# Handheld.net
KiCad netlist of a schematic drawn in EasyEDA
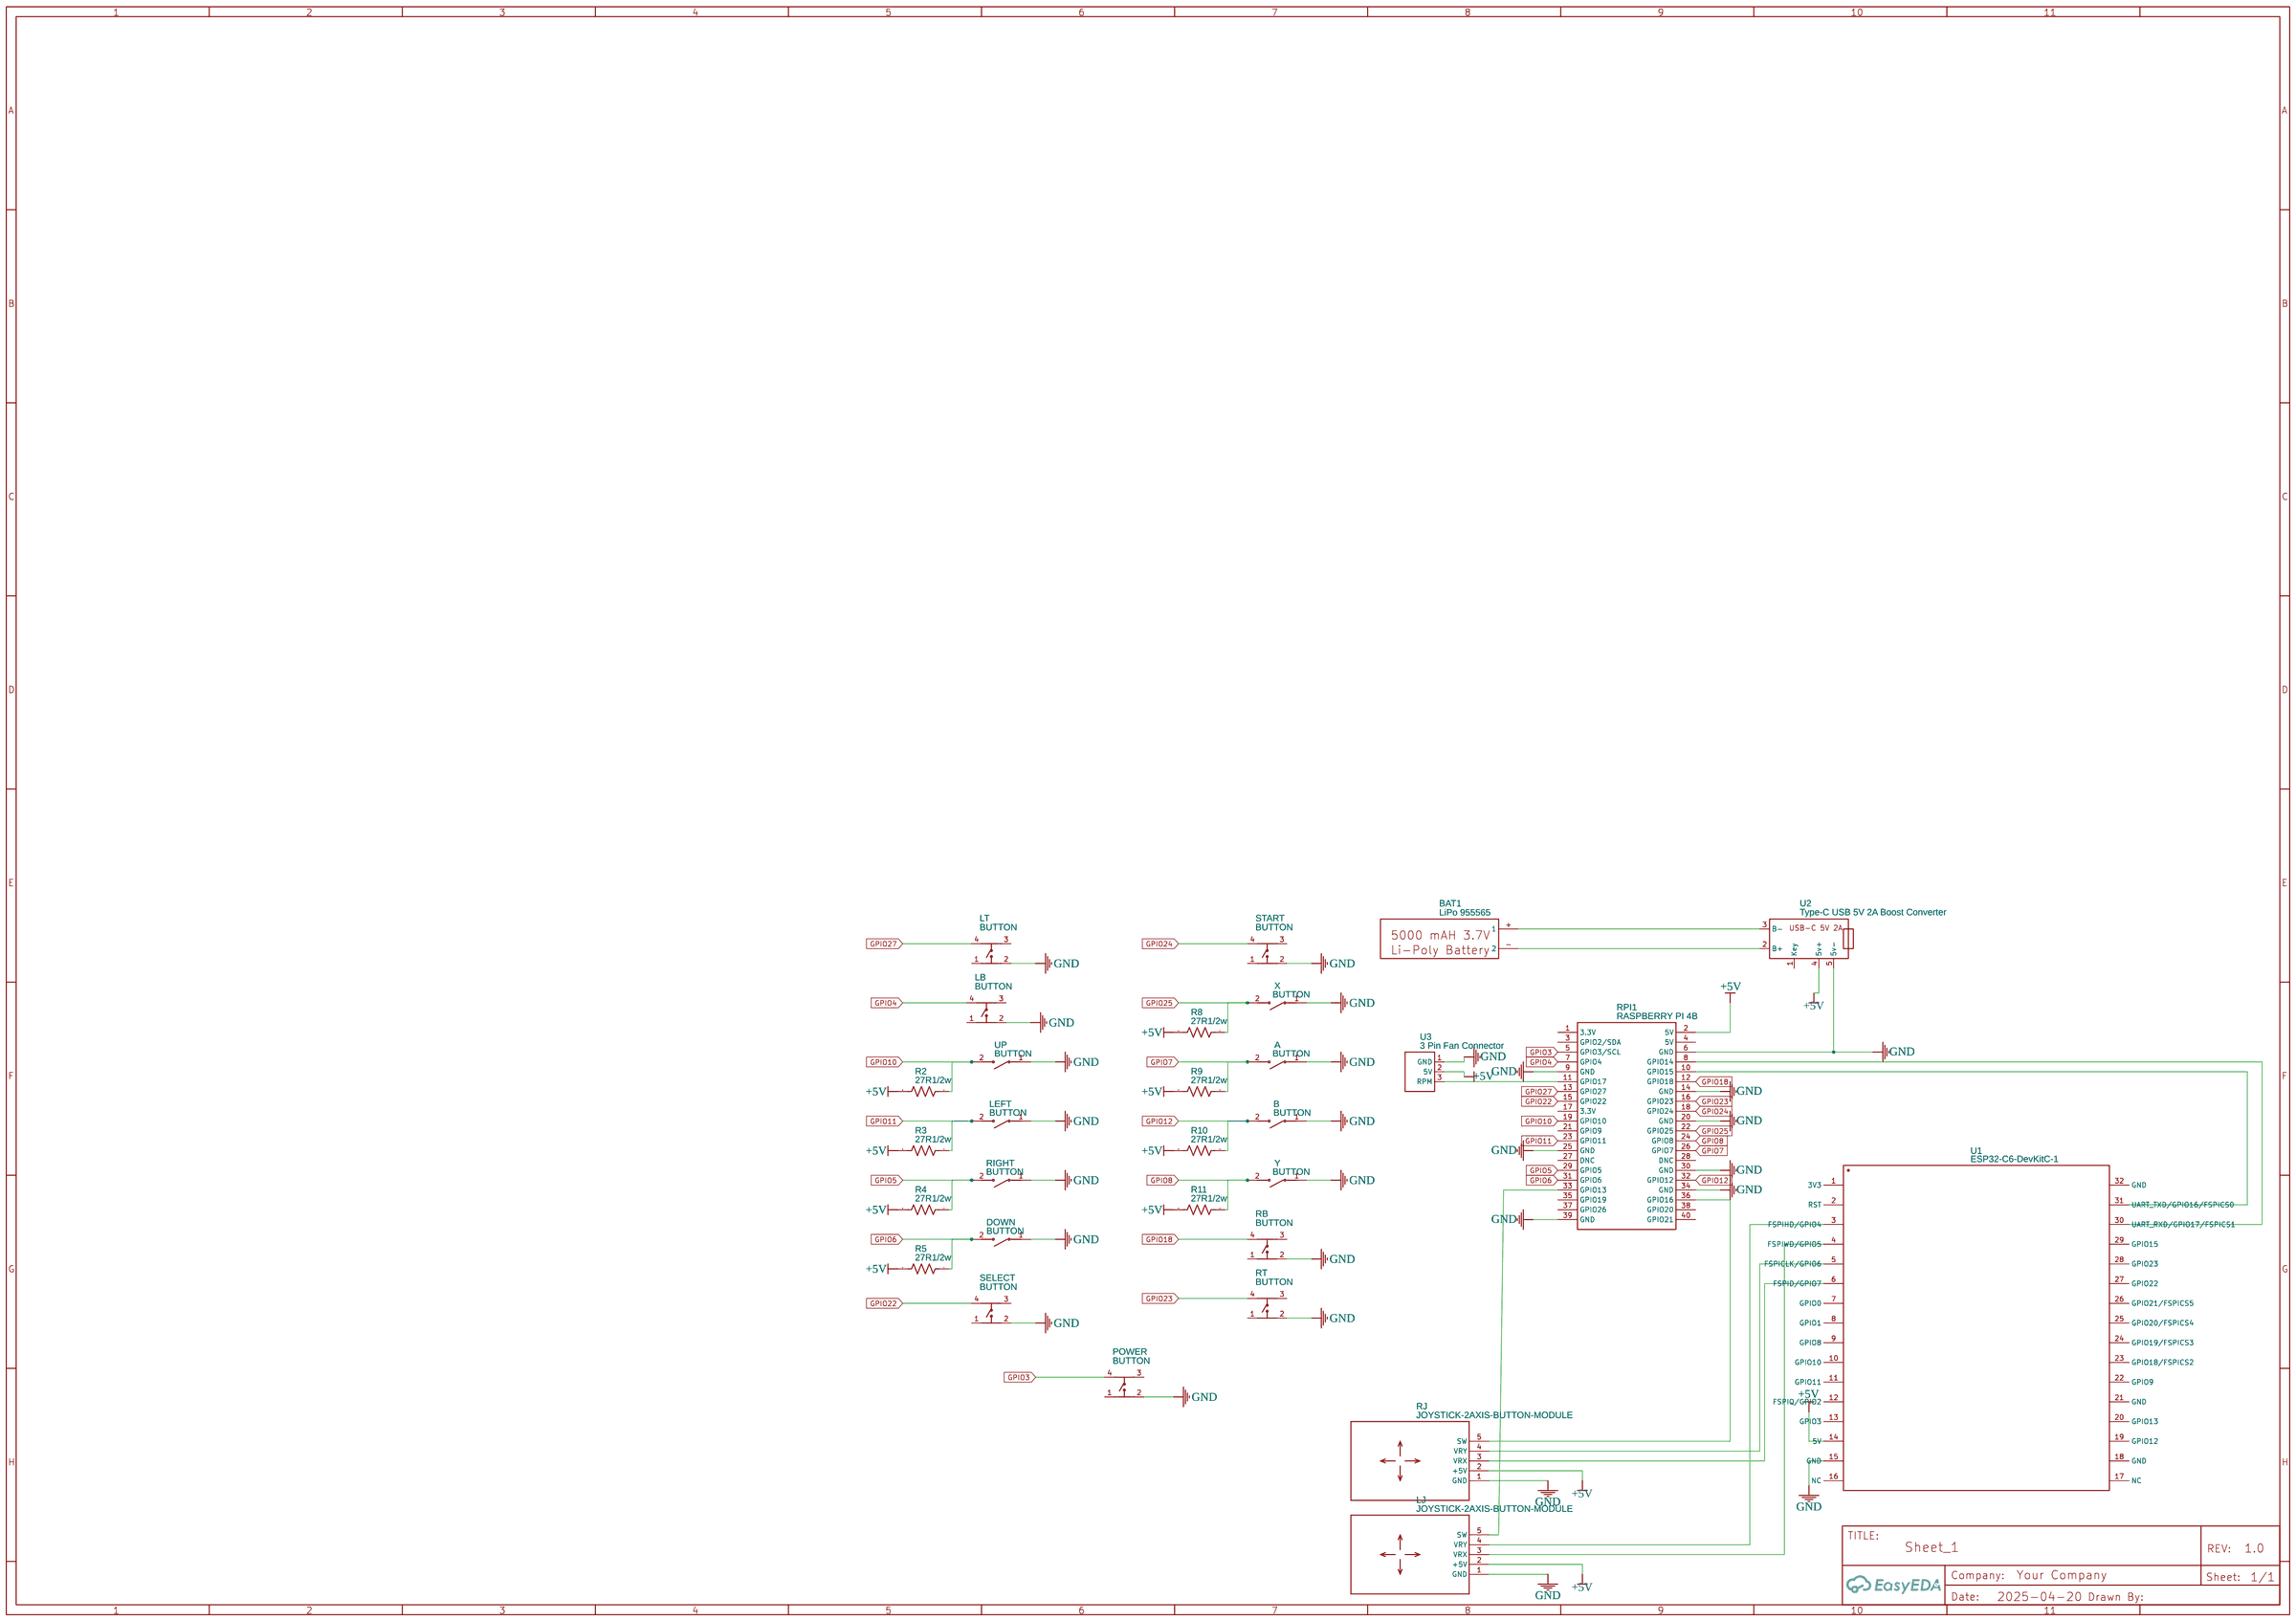
[diagram p0: schematic sheet]

(export (version "E")
  (design (tool "Eeschema 10.0.6"))
  (components
    (comp (ref "A") (value "BUTTON") (libsource (lib "") (part "BUTTON_4")))
    (comp (ref "B") (value "BUTTON") (libsource (lib "") (part "BUTTON_2")))
    (comp (ref "BAT1") (value "LiPo 955565") (libsource (lib "") (part "LiPo 955565")))
    (comp (ref "DOWN") (value "BUTTON") (libsource (lib "") (part "BUTTON_3")))
    (comp (ref "LB")
      (value "BUTTON")
      (fields (field (name "Manufacturer Part") "button6*6*8") (field (name "Manufacturer") "ReliaPro"))
      (libsource (lib "") (part "button6*6*8_5"))
    )
    (comp (ref "LEFT") (value "BUTTON") (libsource (lib "") (part "BUTTON_5")))
    (comp (ref "LJ")
      (value "JOYSTICK-2AXIS-BUTTON-MODULE")
      (libsource (lib "") (part "JOYSTICK-2AXIS-BUTTON-MODULE"))
    )
    (comp (ref "LT")
      (value "BUTTON")
      (fields (field (name "Manufacturer Part") "button6*6*8") (field (name "Manufacturer") "ReliaPro"))
      (libsource (lib "") (part "button6*6*8_6"))
    )
    (comp (ref "POWER")
      (value "BUTTON")
      (fields (field (name "Manufacturer Part") "button6*6*8") (field (name "Manufacturer") "ReliaPro"))
      (libsource (lib "") (part "button6*6*8_1"))
    )
    (comp (ref "R2") (value "27R1/2w") (libsource (lib "") (part "Resistor-1/2w")))
    (comp (ref "R3") (value "27R1/2w") (libsource (lib "") (part "Resistor-1/2w")))
    (comp (ref "R4") (value "27R1/2w") (libsource (lib "") (part "Resistor-1/2w")))
    (comp (ref "R5") (value "27R1/2w") (libsource (lib "") (part "Resistor-1/2w")))
    (comp (ref "R8") (value "27R1/2w") (libsource (lib "") (part "Resistor-1/2w")))
    (comp (ref "R9") (value "27R1/2w") (libsource (lib "") (part "Resistor-1/2w")))
    (comp (ref "R10") (value "27R1/2w") (libsource (lib "") (part "Resistor-1/2w")))
    (comp (ref "R11") (value "27R1/2w") (libsource (lib "") (part "Resistor-1/2w")))
    (comp (ref "RB")
      (value "BUTTON")
      (fields (field (name "Manufacturer Part") "button6*6*8") (field (name "Manufacturer") "ReliaPro"))
      (libsource (lib "") (part "button6*6*8_2"))
    )
    (comp (ref "RIGHT") (value "BUTTON") (libsource (lib "") (part "BUTTON_1")))
    (comp (ref "RJ")
      (value "JOYSTICK-2AXIS-BUTTON-MODULE")
      (libsource (lib "") (part "JOYSTICK-2AXIS-BUTTON-MODULE_1"))
    )
    (comp (ref "RPI1")
      (value "RASPBERRY PI 4B")
      (fields
        (field (name "Manufacturer Part") "Raspberry Pi 4 Model B 2019 Quad Core 64 Bit WiFi Bluetooth (4GB)")
        (field (name "Manufacturer") "Raspberry Pi")
      )
      (libsource (lib "") (part "RASPBERRY PI 4B"))
    )
    (comp (ref "RT")
      (value "BUTTON")
      (fields (field (name "Manufacturer Part") "button6*6*8") (field (name "Manufacturer") "ReliaPro"))
      (libsource (lib "") (part "button6*6*8_4"))
    )
    (comp (ref "SELECT")
      (value "BUTTON")
      (fields (field (name "Manufacturer Part") "button6*6*8") (field (name "Manufacturer") "ReliaPro"))
      (libsource (lib "") (part "button6*6*8_3"))
    )
    (comp (ref "START")
      (value "BUTTON")
      (fields (field (name "Manufacturer Part") "button6*6*8") (field (name "Manufacturer") "ReliaPro"))
      (libsource (lib "") (part "button6*6*8"))
    )
    (comp (ref "U1") (value "ESP32-C6-DevKitC-1") (libsource (lib "") (part "ESP32-C6-DevKitC-1")))
    (comp (ref "U2")
      (value "Type-C USB 5V 2A Boost Converter")
      (fields (field (name "Manufacturer Part") "ELC5060"))
      (libsource (lib "") (part "Type-C USB 5V 2A Boost Converter"))
    )
    (comp (ref "U3")
      (value "3 Pin Fan Connector")
      (fields (field (name "Manufacturer Part") "PSS 254/3W"))
      (libsource (lib "") (part "3 Pin Fan Connector"))
    )
    (comp (ref "UP") (value "BUTTON") (libsource (lib "") (part "BUTTON_6")))
    (comp (ref "X") (value "BUTTON") (libsource (lib "") (part "BUTTON")))
    (comp (ref "Y") (value "BUTTON") (libsource (lib "") (part "BUTTON_7")))
  )
  (nets
    (net (code "1") (name "+5V") (class "Default")
      (node (ref "LJ") (pin "2") (pinfunction "+5V_2") (pintype "bidirectional"))
      (node (ref "R10") (pin "2") (pinfunction "2_2") (pintype "unspecified"))
      (node (ref "R11") (pin "2") (pinfunction "2_2") (pintype "unspecified"))
      (node (ref "R2") (pin "2") (pinfunction "2_2") (pintype "unspecified"))
      (node (ref "R3") (pin "2") (pinfunction "2_2") (pintype "unspecified"))
      (node (ref "R4") (pin "2") (pinfunction "2_2") (pintype "unspecified"))
      (node (ref "R5") (pin "2") (pinfunction "2_2") (pintype "unspecified"))
      (node (ref "R8") (pin "2") (pinfunction "2_2") (pintype "unspecified"))
      (node (ref "R9") (pin "2") (pinfunction "2_2") (pintype "unspecified"))
      (node (ref "RJ") (pin "2") (pinfunction "+5V_2") (pintype "bidirectional"))
      (node (ref "RPI1") (pin "2") (pinfunction "5V_2") (pintype "unspecified"))
      (node (ref "U1") (pin "14") (pinfunction "5V_14") (pintype "unspecified"))
      (node (ref "U2") (pin "4") (pinfunction "5v+_4") (pintype "passive"))
      (node (ref "U3") (pin "2") (pinfunction "5V_2") (pintype "unspecified"))
    )
    (net (code "2") (name "GND") (class "Default")
      (node (ref "A") (pin "1") (pinfunction "1_1") (pintype "unspecified"))
      (node (ref "B") (pin "1") (pinfunction "1_1") (pintype "unspecified"))
      (node (ref "DOWN") (pin "1") (pinfunction "1_1") (pintype "unspecified"))
      (node (ref "LB") (pin "2") (pinfunction "2_2") (pintype "unspecified"))
      (node (ref "LEFT") (pin "1") (pinfunction "1_1") (pintype "unspecified"))
      (node (ref "LJ") (pin "1") (pinfunction "GND_1") (pintype "bidirectional"))
      (node (ref "LT") (pin "2") (pinfunction "2_2") (pintype "unspecified"))
      (node (ref "POWER") (pin "2") (pinfunction "2_2") (pintype "unspecified"))
      (node (ref "RB") (pin "2") (pinfunction "2_2") (pintype "unspecified"))
      (node (ref "RIGHT") (pin "1") (pinfunction "1_1") (pintype "unspecified"))
      (node (ref "RJ") (pin "1") (pinfunction "GND_1") (pintype "bidirectional"))
      (node (ref "RPI1") (pin "14") (pinfunction "GND_14") (pintype "unspecified"))
      (node (ref "RPI1") (pin "20") (pinfunction "GND_20") (pintype "unspecified"))
      (node (ref "RPI1") (pin "25") (pinfunction "GND_25") (pintype "unspecified"))
      (node (ref "RPI1") (pin "30") (pinfunction "GND_30") (pintype "unspecified"))
      (node (ref "RPI1") (pin "34") (pinfunction "GND_34") (pintype "unspecified"))
      (node (ref "RPI1") (pin "39") (pinfunction "GND_39") (pintype "unspecified"))
      (node (ref "RPI1") (pin "6") (pinfunction "GND_6") (pintype "unspecified"))
      (node (ref "RPI1") (pin "9") (pinfunction "GND_9") (pintype "unspecified"))
      (node (ref "RT") (pin "2") (pinfunction "2_2") (pintype "unspecified"))
      (node (ref "SELECT") (pin "2") (pinfunction "2_2") (pintype "unspecified"))
      (node (ref "START") (pin "2") (pinfunction "2_2") (pintype "unspecified"))
      (node (ref "U1") (pin "15") (pinfunction "GND_15") (pintype "unspecified"))
      (node (ref "U2") (pin "5") (pinfunction "5v-_5") (pintype "passive"))
      (node (ref "U3") (pin "1") (pinfunction "GND_1") (pintype "unspecified"))
      (node (ref "UP") (pin "1") (pinfunction "1_1") (pintype "unspecified"))
      (node (ref "X") (pin "1") (pinfunction "1_1") (pintype "unspecified"))
      (node (ref "Y") (pin "1") (pinfunction "1_1") (pintype "unspecified"))
    )
    (net (code "3") (name "GPIO3") (class "Default")
      (node (ref "POWER") (pin "4") (pinfunction "4_4") (pintype "unspecified"))
      (node (ref "RPI1") (pin "5") (pinfunction "GPIO3/SCL_5") (pintype "unspecified"))
    )
    (net (code "4") (name "GPIO4") (class "Default")
      (node (ref "LB") (pin "4") (pinfunction "4_4") (pintype "unspecified"))
      (node (ref "RPI1") (pin "7") (pinfunction "GPIO4_7") (pintype "unspecified"))
    )
    (net (code "5") (name "GPIO5") (class "Default")
      (node (ref "R4") (pin "1") (pinfunction "1_1") (pintype "unspecified"))
      (node (ref "RIGHT") (pin "2") (pinfunction "2_2") (pintype "unspecified"))
      (node (ref "RPI1") (pin "29") (pinfunction "GPIO5_29") (pintype "unspecified"))
    )
    (net (code "6") (name "GPIO6") (class "Default")
      (node (ref "DOWN") (pin "2") (pinfunction "2_2") (pintype "unspecified"))
      (node (ref "R5") (pin "1") (pinfunction "1_1") (pintype "unspecified"))
      (node (ref "RPI1") (pin "31") (pinfunction "GPIO6_31") (pintype "unspecified"))
    )
    (net (code "7") (name "GPIO7") (class "Default")
      (node (ref "A") (pin "2") (pinfunction "2_2") (pintype "unspecified"))
      (node (ref "R9") (pin "1") (pinfunction "1_1") (pintype "unspecified"))
      (node (ref "RPI1") (pin "26") (pinfunction "GPIO7_26") (pintype "unspecified"))
    )
    (net (code "8") (name "GPIO8") (class "Default")
      (node (ref "R11") (pin "1") (pinfunction "1_1") (pintype "unspecified"))
      (node (ref "RPI1") (pin "24") (pinfunction "GPIO8_24") (pintype "unspecified"))
      (node (ref "Y") (pin "2") (pinfunction "2_2") (pintype "unspecified"))
    )
    (net (code "9") (name "GPIO10") (class "Default")
      (node (ref "R2") (pin "1") (pinfunction "1_1") (pintype "unspecified"))
      (node (ref "RPI1") (pin "19") (pinfunction "GPIO10_19") (pintype "unspecified"))
      (node (ref "UP") (pin "2") (pinfunction "2_2") (pintype "unspecified"))
    )
    (net (code "10") (name "GPIO11") (class "Default")
      (node (ref "LEFT") (pin "2") (pinfunction "2_2") (pintype "unspecified"))
      (node (ref "R3") (pin "1") (pinfunction "1_1") (pintype "unspecified"))
      (node (ref "RPI1") (pin "23") (pinfunction "GPIO11_23") (pintype "unspecified"))
    )
    (net (code "11") (name "GPIO12") (class "Default")
      (node (ref "B") (pin "2") (pinfunction "2_2") (pintype "unspecified"))
      (node (ref "R10") (pin "1") (pinfunction "1_1") (pintype "unspecified"))
      (node (ref "RPI1") (pin "32") (pinfunction "GPIO12_32") (pintype "unspecified"))
    )
    (net (code "12") (name "GPIO18") (class "Default")
      (node (ref "RB") (pin "4") (pinfunction "4_4") (pintype "unspecified"))
      (node (ref "RPI1") (pin "12") (pinfunction "GPIO18_12") (pintype "unspecified"))
    )
    (net (code "13") (name "GPIO22") (class "Default")
      (node (ref "RPI1") (pin "15") (pinfunction "GPIO22_15") (pintype "unspecified"))
      (node (ref "SELECT") (pin "4") (pinfunction "4_4") (pintype "unspecified"))
    )
    (net (code "14") (name "GPIO23") (class "Default")
      (node (ref "RPI1") (pin "16") (pinfunction "GPIO23_16") (pintype "unspecified"))
      (node (ref "RT") (pin "4") (pinfunction "4_4") (pintype "unspecified"))
    )
    (net (code "15") (name "GPIO24") (class "Default")
      (node (ref "RPI1") (pin "18") (pinfunction "GPIO24_18") (pintype "unspecified"))
      (node (ref "START") (pin "4") (pinfunction "4_4") (pintype "unspecified"))
    )
    (net (code "16") (name "GPIO25") (class "Default")
      (node (ref "R8") (pin "1") (pinfunction "1_1") (pintype "unspecified"))
      (node (ref "RPI1") (pin "22") (pinfunction "GPIO25_22") (pintype "unspecified"))
      (node (ref "X") (pin "2") (pinfunction "2_2") (pintype "unspecified"))
    )
    (net (code "17") (name "GPIO27") (class "Default")
      (node (ref "LT") (pin "4") (pinfunction "4_4") (pintype "unspecified"))
      (node (ref "RPI1") (pin "13") (pinfunction "GPIO27_13") (pintype "unspecified"))
    )
    (net (code "18") (name "Net-(BAT1-1)") (class "Default")
      (node (ref "BAT1") (pin "+") (pinfunction "1_+") (pintype "unspecified"))
      (node (ref "U2") (pin "3") (pinfunction "B-_3") (pintype "input"))
    )
    (net (code "19") (name "Net-(BAT1-2)") (class "Default")
      (node (ref "BAT1") (pin "-") (pinfunction "2_-") (pintype "unspecified"))
      (node (ref "U2") (pin "2") (pinfunction "B+_2") (pintype "input"))
    )
    (net (code "20") (name "Net-(LJ-SW)") (class "Default")
      (node (ref "LJ") (pin "5") (pinfunction "SW_5") (pintype "bidirectional"))
      (node (ref "RPI1") (pin "33") (pinfunction "GPIO13_33") (pintype "unspecified"))
    )
    (net (code "21") (name "Net-(LJ-VRX)") (class "Default")
      (node (ref "LJ") (pin "3") (pinfunction "VRX_3") (pintype "bidirectional"))
      (node (ref "U1") (pin "4") (pinfunction "FSPIWD/GPIO5_4") (pintype "unspecified"))
    )
    (net (code "22") (name "Net-(LJ-VRY)") (class "Default")
      (node (ref "LJ") (pin "4") (pinfunction "VRY_4") (pintype "bidirectional"))
      (node (ref "U1") (pin "3") (pinfunction "FSPIHD/GPIO4_3") (pintype "unspecified"))
    )
    (net (code "23") (name "Net-(RJ-SW)") (class "Default")
      (node (ref "RJ") (pin "5") (pinfunction "SW_5") (pintype "bidirectional"))
      (node (ref "RPI1") (pin "36") (pinfunction "GPIO16_36") (pintype "unspecified"))
    )
    (net (code "24") (name "Net-(RJ-VRX)") (class "Default")
      (node (ref "RJ") (pin "3") (pinfunction "VRX_3") (pintype "bidirectional"))
      (node (ref "U1") (pin "6") (pinfunction "FSPID/GPIO7_6") (pintype "unspecified"))
    )
    (net (code "25") (name "Net-(RJ-VRY)") (class "Default")
      (node (ref "RJ") (pin "4") (pinfunction "VRY_4") (pintype "bidirectional"))
      (node (ref "U1") (pin "5") (pinfunction "FSPICLK/GPIO6_5") (pintype "unspecified"))
    )
    (net (code "26") (name "Net-(RPI1-GPIO14)") (class "Default")
      (node (ref "RPI1") (pin "8") (pinfunction "GPIO14_8") (pintype "unspecified"))
      (node (ref "U1") (pin "30") (pinfunction "UART_RXD/GPIO17/FSPICS1_30") (pintype "unspecified"))
    )
    (net (code "27") (name "Net-(RPI1-GPIO15)") (class "Default")
      (node (ref "RPI1") (pin "10") (pinfunction "GPIO15_10") (pintype "unspecified"))
      (node (ref "U1") (pin "31") (pinfunction "UART_TXD/GPIO16/FSPICS0_31") (pintype "unspecified"))
    )
    (net (code "28") (name "Net-(RPI1-GPIO17)") (class "Default")
      (node (ref "RPI1") (pin "11") (pinfunction "GPIO17_11") (pintype "unspecified"))
      (node (ref "U3") (pin "3") (pinfunction "RPM_3") (pintype "unspecified"))
    )
    (net (code "29") (name "unconnected-(LB-Pad1)") (class "Default")
      (node (ref "LB") (pin "1") (pinfunction "1_1") (pintype "unspecified"))
    )
    (net (code "30") (name "unconnected-(LB-Pad3)") (class "Default")
      (node (ref "LB") (pin "3") (pinfunction "3_3") (pintype "unspecified"))
    )
    (net (code "31") (name "unconnected-(LT-Pad1)") (class "Default")
      (node (ref "LT") (pin "1") (pinfunction "1_1") (pintype "unspecified"))
    )
    (net (code "32") (name "unconnected-(LT-Pad3)") (class "Default")
      (node (ref "LT") (pin "3") (pinfunction "3_3") (pintype "unspecified"))
    )
    (net (code "33") (name "unconnected-(POWER-Pad1)") (class "Default")
      (node (ref "POWER") (pin "1") (pinfunction "1_1") (pintype "unspecified"))
    )
    (net (code "34") (name "unconnected-(POWER-Pad3)") (class "Default")
      (node (ref "POWER") (pin "3") (pinfunction "3_3") (pintype "unspecified"))
    )
    (net (code "35") (name "unconnected-(RB-Pad1)") (class "Default")
      (node (ref "RB") (pin "1") (pinfunction "1_1") (pintype "unspecified"))
    )
    (net (code "36") (name "unconnected-(RB-Pad3)") (class "Default")
      (node (ref "RB") (pin "3") (pinfunction "3_3") (pintype "unspecified"))
    )
    (net (code "37") (name "unconnected-(RPI1-3.3V-Pad1)") (class "Default")
      (node (ref "RPI1") (pin "1") (pinfunction "3.3V_1") (pintype "unspecified"))
    )
    (net (code "38") (name "unconnected-(RPI1-3.3V-Pad17)") (class "Default")
      (node (ref "RPI1") (pin "17") (pinfunction "3.3V_17") (pintype "unspecified"))
    )
    (net (code "39") (name "unconnected-(RPI1-5V-Pad4)") (class "Default")
      (node (ref "RPI1") (pin "4") (pinfunction "5V_4") (pintype "unspecified"))
    )
    (net (code "40") (name "unconnected-(RPI1-DNC-Pad27)") (class "Default")
      (node (ref "RPI1") (pin "27") (pinfunction "DNC_27") (pintype "unspecified"))
    )
    (net (code "41") (name "unconnected-(RPI1-DNC-Pad28)") (class "Default")
      (node (ref "RPI1") (pin "28") (pinfunction "DNC_28") (pintype "unspecified"))
    )
    (net (code "42") (name "unconnected-(RPI1-GPIO2{slash}SDA-Pad3)") (class "Default")
      (node (ref "RPI1") (pin "3") (pinfunction "GPIO2/SDA_3") (pintype "unspecified"))
    )
    (net (code "43") (name "unconnected-(RPI1-GPIO9-Pad21)") (class "Default")
      (node (ref "RPI1") (pin "21") (pinfunction "GPIO9_21") (pintype "unspecified"))
    )
    (net (code "44") (name "unconnected-(RPI1-GPIO19-Pad35)") (class "Default")
      (node (ref "RPI1") (pin "35") (pinfunction "GPIO19_35") (pintype "unspecified"))
    )
    (net (code "45") (name "unconnected-(RPI1-GPIO20-Pad38)") (class "Default")
      (node (ref "RPI1") (pin "38") (pinfunction "GPIO20_38") (pintype "unspecified"))
    )
    (net (code "46") (name "unconnected-(RPI1-GPIO21-Pad40)") (class "Default")
      (node (ref "RPI1") (pin "40") (pinfunction "GPIO21_40") (pintype "unspecified"))
    )
    (net (code "47") (name "unconnected-(RPI1-GPIO26-Pad37)") (class "Default")
      (node (ref "RPI1") (pin "37") (pinfunction "GPIO26_37") (pintype "unspecified"))
    )
    (net (code "48") (name "unconnected-(RT-Pad1)") (class "Default")
      (node (ref "RT") (pin "1") (pinfunction "1_1") (pintype "unspecified"))
    )
    (net (code "49") (name "unconnected-(RT-Pad3)") (class "Default")
      (node (ref "RT") (pin "3") (pinfunction "3_3") (pintype "unspecified"))
    )
    (net (code "50") (name "unconnected-(SELECT-Pad1)") (class "Default")
      (node (ref "SELECT") (pin "1") (pinfunction "1_1") (pintype "unspecified"))
    )
    (net (code "51") (name "unconnected-(SELECT-Pad3)") (class "Default")
      (node (ref "SELECT") (pin "3") (pinfunction "3_3") (pintype "unspecified"))
    )
    (net (code "52") (name "unconnected-(START-Pad1)") (class "Default")
      (node (ref "START") (pin "1") (pinfunction "1_1") (pintype "unspecified"))
    )
    (net (code "53") (name "unconnected-(START-Pad3)") (class "Default")
      (node (ref "START") (pin "3") (pinfunction "3_3") (pintype "unspecified"))
    )
    (net (code "54") (name "unconnected-(U1-3V3-Pad1)") (class "Default")
      (node (ref "U1") (pin "1") (pinfunction "3V3_1") (pintype "unspecified"))
    )
    (net (code "55") (name "unconnected-(U1-FSPIQ{slash}GPIO2-Pad12)") (class "Default")
      (node (ref "U1") (pin "12") (pinfunction "FSPIQ/GPIO2_12") (pintype "unspecified"))
    )
    (net (code "56") (name "unconnected-(U1-GND-Pad18)") (class "Default")
      (node (ref "U1") (pin "18") (pinfunction "GND_18") (pintype "unspecified"))
    )
    (net (code "57") (name "unconnected-(U1-GND-Pad21)") (class "Default")
      (node (ref "U1") (pin "21") (pinfunction "GND_21") (pintype "unspecified"))
    )
    (net (code "58") (name "unconnected-(U1-GND-Pad32)") (class "Default")
      (node (ref "U1") (pin "32") (pinfunction "GND_32") (pintype "unspecified"))
    )
    (net (code "59") (name "unconnected-(U1-GPIO0-Pad7)") (class "Default")
      (node (ref "U1") (pin "7") (pinfunction "GPIO0_7") (pintype "unspecified"))
    )
    (net (code "60") (name "unconnected-(U1-GPIO1-Pad8)") (class "Default")
      (node (ref "U1") (pin "8") (pinfunction "GPIO1_8") (pintype "unspecified"))
    )
    (net (code "61") (name "unconnected-(U1-GPIO3-Pad13)") (class "Default")
      (node (ref "U1") (pin "13") (pinfunction "GPIO3_13") (pintype "unspecified"))
    )
    (net (code "62") (name "unconnected-(U1-GPIO8-Pad9)") (class "Default")
      (node (ref "U1") (pin "9") (pinfunction "GPIO8_9") (pintype "unspecified"))
    )
    (net (code "63") (name "unconnected-(U1-GPIO9-Pad22)") (class "Default")
      (node (ref "U1") (pin "22") (pinfunction "GPIO9_22") (pintype "unspecified"))
    )
    (net (code "64") (name "unconnected-(U1-GPIO10-Pad10)") (class "Default")
      (node (ref "U1") (pin "10") (pinfunction "GPIO10_10") (pintype "unspecified"))
    )
    (net (code "65") (name "unconnected-(U1-GPIO11-Pad11)") (class "Default")
      (node (ref "U1") (pin "11") (pinfunction "GPIO11_11") (pintype "unspecified"))
    )
    (net (code "66") (name "unconnected-(U1-GPIO12-Pad19)") (class "Default")
      (node (ref "U1") (pin "19") (pinfunction "GPIO12_19") (pintype "unspecified"))
    )
    (net (code "67") (name "unconnected-(U1-GPIO13-Pad20)") (class "Default")
      (node (ref "U1") (pin "20") (pinfunction "GPIO13_20") (pintype "unspecified"))
    )
    (net (code "68") (name "unconnected-(U1-GPIO15-Pad29)") (class "Default")
      (node (ref "U1") (pin "29") (pinfunction "GPIO15_29") (pintype "unspecified"))
    )
    (net (code "69") (name "unconnected-(U1-GPIO18{slash}FSPICS2-Pad23)") (class "Default")
      (node (ref "U1") (pin "23") (pinfunction "GPIO18/FSPICS2_23") (pintype "unspecified"))
    )
    (net (code "70") (name "unconnected-(U1-GPIO19{slash}FSPICS3-Pad24)") (class "Default")
      (node (ref "U1") (pin "24") (pinfunction "GPIO19/FSPICS3_24") (pintype "unspecified"))
    )
    (net (code "71") (name "unconnected-(U1-GPIO20{slash}FSPICS4-Pad25)") (class "Default")
      (node (ref "U1") (pin "25") (pinfunction "GPIO20/FSPICS4_25") (pintype "unspecified"))
    )
    (net (code "72") (name "unconnected-(U1-GPIO21{slash}FSPICS5-Pad26)") (class "Default")
      (node (ref "U1") (pin "26") (pinfunction "GPIO21/FSPICS5_26") (pintype "unspecified"))
    )
    (net (code "73") (name "unconnected-(U1-GPIO22-Pad27)") (class "Default")
      (node (ref "U1") (pin "27") (pinfunction "GPIO22_27") (pintype "unspecified"))
    )
    (net (code "74") (name "unconnected-(U1-GPIO23-Pad28)") (class "Default")
      (node (ref "U1") (pin "28") (pinfunction "GPIO23_28") (pintype "unspecified"))
    )
    (net (code "75") (name "unconnected-(U1-NC-Pad16)") (class "Default")
      (node (ref "U1") (pin "16") (pinfunction "NC_16") (pintype "unspecified"))
    )
    (net (code "76") (name "unconnected-(U1-NC-Pad17)") (class "Default")
      (node (ref "U1") (pin "17") (pinfunction "NC_17") (pintype "unspecified"))
    )
    (net (code "77") (name "unconnected-(U1-RST-Pad2)") (class "Default")
      (node (ref "U1") (pin "2") (pinfunction "RST_2") (pintype "unspecified"))
    )
    (net (code "78") (name "unconnected-(U2-Key-Pad1)") (class "Default")
      (node (ref "U2") (pin "1") (pinfunction "Key_1") (pintype "bidirectional"))
    )
  )
)
